# pda6502.net
KiCad netlist of a schematic drawn in EAGLE
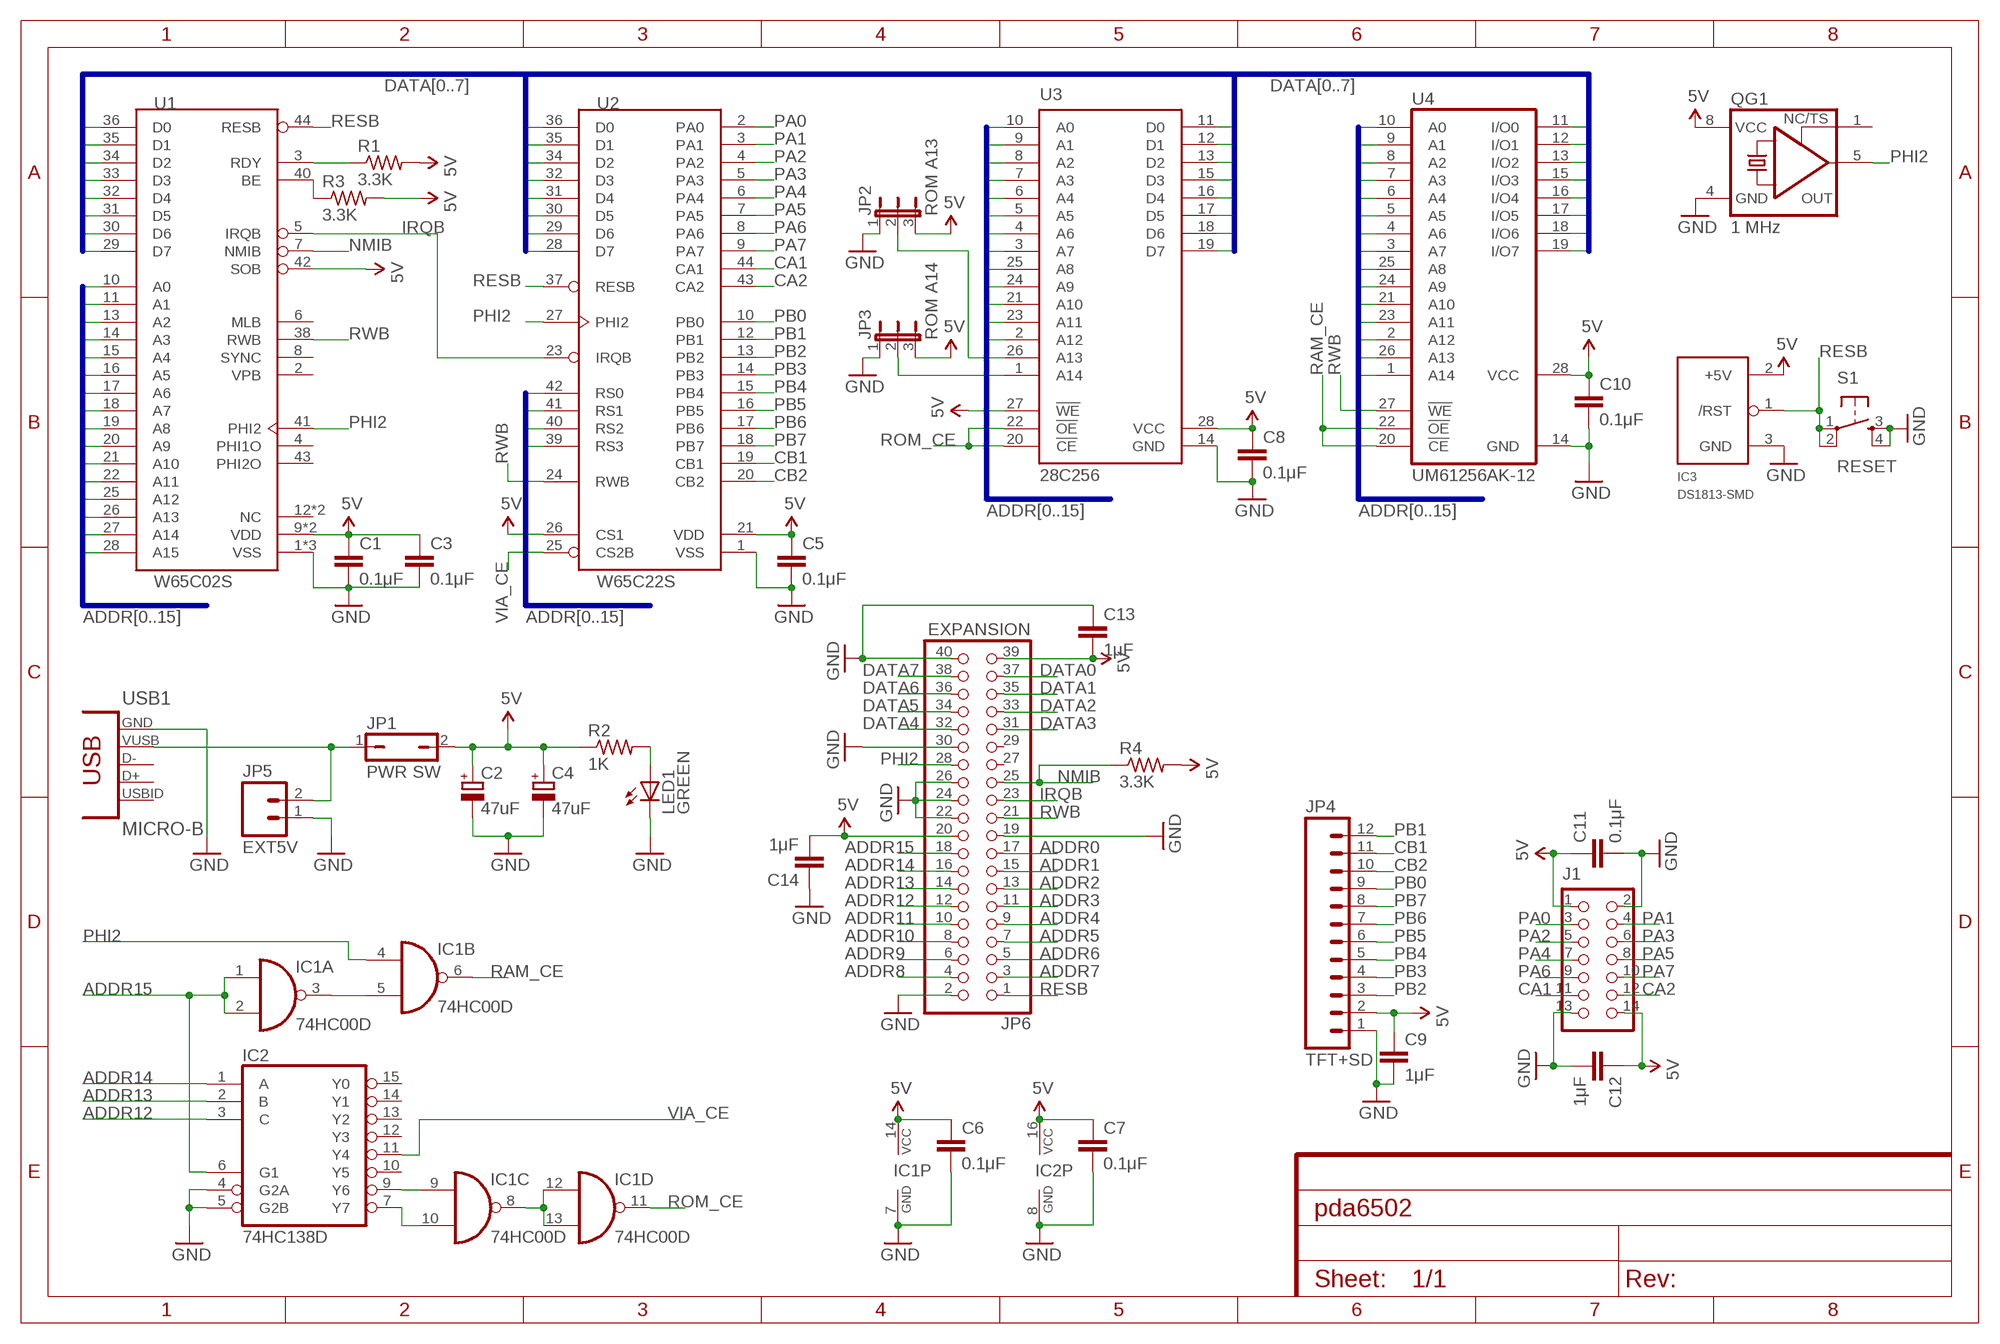
[diagram p0: schematic, sheet 1]

(export (version "E")
  (design (tool "Eeschema 10.0.6"))
  (components
    (comp (ref "C1")
      (value "0.1μF")
      (footprint "eagle-import:C0805")
      (libsource (lib "eagle-import") (part "C-EUC0805"))
    )
    (comp (ref "C2")
      (value "47uF")
      (footprint "eagle-import:CASE_B")
      (libsource (lib "eagle-import") (part "CAPACITOR_POL-CASE_B"))
    )
    (comp (ref "C3")
      (value "0.1μF")
      (footprint "eagle-import:C0805")
      (libsource (lib "eagle-import") (part "C-EUC0805"))
    )
    (comp (ref "C4")
      (value "47uF")
      (footprint "eagle-import:CASE_B")
      (libsource (lib "eagle-import") (part "CAPACITOR_POL-CASE_B"))
    )
    (comp (ref "C5")
      (value "0.1μF")
      (footprint "eagle-import:C0805")
      (libsource (lib "eagle-import") (part "C-EUC0805"))
    )
    (comp (ref "C6")
      (value "0.1μF")
      (footprint "eagle-import:C0805")
      (libsource (lib "eagle-import") (part "C-EUC0805"))
    )
    (comp (ref "C7")
      (value "0.1μF")
      (footprint "eagle-import:C0805")
      (libsource (lib "eagle-import") (part "C-EUC0805"))
    )
    (comp (ref "C8")
      (value "0.1μF")
      (footprint "eagle-import:C0805")
      (libsource (lib "eagle-import") (part "C-EUC0805"))
    )
    (comp (ref "C9")
      (value "1μF")
      (footprint "eagle-import:C0805")
      (libsource (lib "eagle-import") (part "C-EUC0805"))
    )
    (comp (ref "C10")
      (value "0.1μF")
      (footprint "eagle-import:C0805")
      (libsource (lib "eagle-import") (part "C-EUC0805"))
    )
    (comp (ref "C11")
      (value "0.1μF")
      (footprint "eagle-import:C0805")
      (libsource (lib "eagle-import") (part "C-EUC0805"))
    )
    (comp (ref "C12")
      (value "1μF")
      (footprint "eagle-import:C0805")
      (libsource (lib "eagle-import") (part "C-EUC0805"))
    )
    (comp (ref "C13")
      (value "1μF")
      (footprint "eagle-import:C0805")
      (libsource (lib "eagle-import") (part "C-EUC0805"))
    )
    (comp (ref "C14")
      (value "1μF")
      (footprint "eagle-import:C0805")
      (libsource (lib "eagle-import") (part "C-EUC0805"))
    )
    (comp (ref "IC1")
      (value "74HC00D")
      (footprint "eagle-import:SO14")
      (libsource (lib "eagle-import") (part "7400DHC"))
    )
    (comp (ref "IC2")
      (value "74HC138D")
      (footprint "eagle-import:SO16")
      (libsource (lib "eagle-import") (part "74138DHC"))
    )
    (comp (ref "IC3")
      (value "DS1813-SMD")
      (footprint "eagle-import:SOT-23")
      (libsource (lib "eagle-import") (part "DS1813-SMD"))
    )
    (comp (ref "J1")
      (value "CON_HEADER_2X07-PTH")
      (footprint "eagle-import:M2X7")
      (libsource (lib "eagle-import") (part "CON_HEADER_2X07-PTH"))
    )
    (comp (ref "JP1")
      (value "PWR SW")
      (footprint "eagle-import:JMP-1X2")
      (libsource (lib "eagle-import") (part "JMP-1X2TH"))
    )
    (comp (ref "JP2")
      (value "ROM A13")
      (footprint "eagle-import:JP2")
      (libsource (lib "eagle-import") (part "JP2E"))
    )
    (comp (ref "JP3")
      (value "ROM A14")
      (footprint "eagle-import:JP2")
      (libsource (lib "eagle-import") (part "JP2E"))
    )
    (comp (ref "JP4")
      (value "TFT+SD")
      (footprint "eagle-import:1X12_NO_SILK_KIT")
      (libsource (lib "eagle-import") (part "M121X12_NO_SILK_KIT"))
    )
    (comp (ref "JP5")
      (value "EXT5V")
      (footprint "eagle-import:1X02")
      (libsource (lib "eagle-import") (part "M02PTH"))
    )
    (comp (ref "JP6")
      (value "EXPANSION")
      (footprint "eagle-import:2X20")
      (libsource (lib "eagle-import") (part "PINHD-2X20"))
    )
    (comp (ref "LED1")
      (value "GREEN")
      (footprint "eagle-import:LED-805")
      (libsource (lib "eagle-import") (part "LED-0805"))
    )
    (comp (ref "QG1")
      (value "1 MHz")
      (footprint "eagle-import:DIL08S")
      (libsource (lib "eagle-import") (part "XO-8"))
    )
    (comp (ref "R1")
      (value "3.3K")
      (footprint "eagle-import:R0805")
      (libsource (lib "eagle-import") (part "R-US_R0805"))
    )
    (comp (ref "R2")
      (value "1K")
      (footprint "eagle-import:R0805")
      (libsource (lib "eagle-import") (part "R-US_R0805"))
    )
    (comp (ref "R3")
      (value "3.3K")
      (footprint "eagle-import:R0805")
      (libsource (lib "eagle-import") (part "R-US_R0805"))
    )
    (comp (ref "R4")
      (value "3.3K")
      (footprint "eagle-import:R0805")
      (libsource (lib "eagle-import") (part "R-US_R0805"))
    )
    (comp (ref "S1")
      (value "RESET")
      (footprint "eagle-import:TACTILE-SWITCH-SMD")
      (libsource (lib "eagle-import") (part "TAC_SWITCHSMD"))
    )
    (comp (ref "U1")
      (value "W65C02S")
      (footprint "eagle-import:PLCC44-SOCKET")
      (libsource (lib "eagle-import") (part "W65C02PLCC44"))
    )
    (comp (ref "U2")
      (value "W65C22S")
      (footprint "eagle-import:PLCC44-SOCKET")
      (libsource (lib "eagle-import") (part "W65C22PLCC44-SOCKET"))
    )
    (comp (ref "U3")
      (value "28C256")
      (footprint "eagle-import:ZIF28-6-WIDE")
      (libsource (lib "eagle-import") (part "28C256-ZIF"))
    )
    (comp (ref "U4")
      (value "UM61256AK-12")
      (footprint "eagle-import:DIL28-3")
      (libsource (lib "eagle-import") (part "UM61256AK-12"))
    )
    (comp (ref "USB1")
      (value "MICRO-B")
      (footprint "eagle-import:CONN_USB_MICRO-B")
      (libsource (lib "eagle-import") (part "CON-USB-F-MICRO-B"))
    )
  )
  (nets
    (net (code "1") (name "/ADDR0") (class "Default")
      (node (ref "JP6") (pin "17") (pinfunction "17_17") (pintype "passive"))
      (node (ref "U1") (pin "10") (pinfunction "A0_10") (pintype "output"))
      (node (ref "U2") (pin "42") (pinfunction "RS0_42") (pintype "input"))
      (node (ref "U3") (pin "10") (pinfunction "A0_10") (pintype "input"))
      (node (ref "U4") (pin "10") (pinfunction "A0_10") (pintype "input"))
    )
    (net (code "2") (name "/ADDR1") (class "Default")
      (node (ref "JP6") (pin "15") (pinfunction "15_15") (pintype "passive"))
      (node (ref "U1") (pin "11") (pinfunction "A1_11") (pintype "output"))
      (node (ref "U2") (pin "41") (pinfunction "RS1_41") (pintype "input"))
      (node (ref "U3") (pin "9") (pinfunction "A1_9") (pintype "input"))
      (node (ref "U4") (pin "9") (pinfunction "A1_9") (pintype "input"))
    )
    (net (code "3") (name "/ADDR2") (class "Default")
      (node (ref "JP6") (pin "13") (pinfunction "13_13") (pintype "passive"))
      (node (ref "U1") (pin "13") (pinfunction "A2_13") (pintype "output"))
      (node (ref "U2") (pin "40") (pinfunction "RS2_40") (pintype "input"))
      (node (ref "U3") (pin "8") (pinfunction "A2_8") (pintype "input"))
      (node (ref "U4") (pin "8") (pinfunction "A2_8") (pintype "input"))
    )
    (net (code "4") (name "/ADDR3") (class "Default")
      (node (ref "JP6") (pin "11") (pinfunction "11_11") (pintype "passive"))
      (node (ref "U1") (pin "14") (pinfunction "A3_14") (pintype "output"))
      (node (ref "U2") (pin "39") (pinfunction "RS3_39") (pintype "input"))
      (node (ref "U3") (pin "7") (pinfunction "A3_7") (pintype "input"))
      (node (ref "U4") (pin "7") (pinfunction "A3_7") (pintype "input"))
    )
    (net (code "5") (name "/ADDR4") (class "Default")
      (node (ref "JP6") (pin "9") (pinfunction "9_9") (pintype "passive"))
      (node (ref "U1") (pin "15") (pinfunction "A4_15") (pintype "output"))
      (node (ref "U3") (pin "6") (pinfunction "A4_6") (pintype "input"))
      (node (ref "U4") (pin "6") (pinfunction "A4_6") (pintype "input"))
    )
    (net (code "6") (name "/ADDR5") (class "Default")
      (node (ref "JP6") (pin "7") (pinfunction "7_7") (pintype "passive"))
      (node (ref "U1") (pin "16") (pinfunction "A5_16") (pintype "output"))
      (node (ref "U3") (pin "5") (pinfunction "A5_5") (pintype "input"))
      (node (ref "U4") (pin "5") (pinfunction "A5_5") (pintype "input"))
    )
    (net (code "7") (name "/ADDR6") (class "Default")
      (node (ref "JP6") (pin "5") (pinfunction "5_5") (pintype "passive"))
      (node (ref "U1") (pin "17") (pinfunction "A6_17") (pintype "output"))
      (node (ref "U3") (pin "4") (pinfunction "A6_4") (pintype "input"))
      (node (ref "U4") (pin "4") (pinfunction "A6_4") (pintype "input"))
    )
    (net (code "8") (name "/ADDR7") (class "Default")
      (node (ref "JP6") (pin "3") (pinfunction "3_3") (pintype "passive"))
      (node (ref "U1") (pin "18") (pinfunction "A7_18") (pintype "output"))
      (node (ref "U3") (pin "3") (pinfunction "A7_3") (pintype "input"))
      (node (ref "U4") (pin "3") (pinfunction "A7_3") (pintype "input"))
    )
    (net (code "9") (name "/ADDR8") (class "Default")
      (node (ref "JP6") (pin "4") (pinfunction "4_4") (pintype "passive"))
      (node (ref "U1") (pin "19") (pinfunction "A8_19") (pintype "output"))
      (node (ref "U3") (pin "25") (pinfunction "A8_25") (pintype "input"))
      (node (ref "U4") (pin "25") (pinfunction "A8_25") (pintype "input"))
    )
    (net (code "10") (name "/ADDR9") (class "Default")
      (node (ref "JP6") (pin "6") (pinfunction "6_6") (pintype "passive"))
      (node (ref "U1") (pin "20") (pinfunction "A9_20") (pintype "output"))
      (node (ref "U3") (pin "24") (pinfunction "A9_24") (pintype "input"))
      (node (ref "U4") (pin "24") (pinfunction "A9_24") (pintype "input"))
    )
    (net (code "11") (name "/ADDR10") (class "Default")
      (node (ref "JP6") (pin "8") (pinfunction "8_8") (pintype "passive"))
      (node (ref "U1") (pin "21") (pinfunction "A10_21") (pintype "output"))
      (node (ref "U3") (pin "21") (pinfunction "A10_21") (pintype "input"))
      (node (ref "U4") (pin "21") (pinfunction "A10_21") (pintype "input"))
    )
    (net (code "12") (name "/ADDR11") (class "Default")
      (node (ref "JP6") (pin "10") (pinfunction "10_10") (pintype "passive"))
      (node (ref "U1") (pin "22") (pinfunction "A11_22") (pintype "output"))
      (node (ref "U3") (pin "23") (pinfunction "A11_23") (pintype "input"))
      (node (ref "U4") (pin "23") (pinfunction "A11_23") (pintype "input"))
    )
    (net (code "13") (name "/ADDR12") (class "Default")
      (node (ref "IC2") (pin "3") (pinfunction "C_3") (pintype "input"))
      (node (ref "JP6") (pin "12") (pinfunction "12_12") (pintype "passive"))
      (node (ref "U1") (pin "25") (pinfunction "A12_25") (pintype "output"))
      (node (ref "U3") (pin "2") (pinfunction "A12_2") (pintype "input"))
      (node (ref "U4") (pin "2") (pinfunction "A12_2") (pintype "input"))
    )
    (net (code "14") (name "/ADDR13") (class "Default")
      (node (ref "IC2") (pin "2") (pinfunction "B_2") (pintype "input"))
      (node (ref "JP6") (pin "14") (pinfunction "14_14") (pintype "passive"))
      (node (ref "U1") (pin "26") (pinfunction "A13_26") (pintype "output"))
      (node (ref "U4") (pin "26") (pinfunction "A13_26") (pintype "input"))
    )
    (net (code "15") (name "/ADDR14") (class "Default")
      (node (ref "IC2") (pin "1") (pinfunction "A_1") (pintype "input"))
      (node (ref "JP6") (pin "16") (pinfunction "16_16") (pintype "passive"))
      (node (ref "U1") (pin "27") (pinfunction "A14_27") (pintype "output"))
      (node (ref "U4") (pin "1") (pinfunction "A14_1") (pintype "input"))
    )
    (net (code "16") (name "/ADDR15") (class "Default")
      (node (ref "IC1") (pin "1") (pinfunction "I0_1") (pintype "input"))
      (node (ref "IC1") (pin "2") (pinfunction "I1_2") (pintype "input"))
      (node (ref "IC2") (pin "6") (pinfunction "G1_6") (pintype "input"))
      (node (ref "JP6") (pin "18") (pinfunction "18_18") (pintype "passive"))
      (node (ref "U1") (pin "28") (pinfunction "A15_28") (pintype "output"))
    )
    (net (code "18") (name "/CA1") (class "Default")
      (node (ref "J1") (pin "11") (pinfunction "11_11") (pintype "passive"))
      (node (ref "U2") (pin "44") (pinfunction "CA1_44") (pintype "input"))
    )
    (net (code "19") (name "/CA2") (class "Default")
      (node (ref "J1") (pin "12") (pinfunction "12_12") (pintype "passive"))
      (node (ref "U2") (pin "43") (pinfunction "CA2_43") (pintype "bidirectional"))
    )
    (net (code "20") (name "/CB1") (class "Default")
      (node (ref "JP4") (pin "11") (pinfunction "11_11") (pintype "passive"))
      (node (ref "U2") (pin "19") (pinfunction "CB1_19") (pintype "input"))
    )
    (net (code "21") (name "/CB2") (class "Default")
      (node (ref "JP4") (pin "10") (pinfunction "10_10") (pintype "passive"))
      (node (ref "U2") (pin "20") (pinfunction "CB2_20") (pintype "bidirectional"))
    )
    (net (code "22") (name "/DATA0") (class "Default")
      (node (ref "JP6") (pin "37") (pinfunction "37_37") (pintype "passive"))
      (node (ref "U1") (pin "36") (pinfunction "D0_36") (pintype "bidirectional"))
      (node (ref "U2") (pin "36") (pinfunction "D0_36") (pintype "bidirectional"))
      (node (ref "U3") (pin "11") (pinfunction "D0_11") (pintype "tri_state"))
      (node (ref "U4") (pin "11") (pinfunction "I/O0_11") (pintype "bidirectional"))
    )
    (net (code "23") (name "/DATA1") (class "Default")
      (node (ref "JP6") (pin "35") (pinfunction "35_35") (pintype "passive"))
      (node (ref "U1") (pin "35") (pinfunction "D1_35") (pintype "bidirectional"))
      (node (ref "U2") (pin "35") (pinfunction "D1_35") (pintype "bidirectional"))
      (node (ref "U3") (pin "12") (pinfunction "D1_12") (pintype "tri_state"))
      (node (ref "U4") (pin "12") (pinfunction "I/O1_12") (pintype "bidirectional"))
    )
    (net (code "24") (name "/DATA2") (class "Default")
      (node (ref "JP6") (pin "33") (pinfunction "33_33") (pintype "passive"))
      (node (ref "U1") (pin "34") (pinfunction "D2_34") (pintype "bidirectional"))
      (node (ref "U2") (pin "34") (pinfunction "D2_34") (pintype "bidirectional"))
      (node (ref "U3") (pin "13") (pinfunction "D2_13") (pintype "tri_state"))
      (node (ref "U4") (pin "13") (pinfunction "I/O2_13") (pintype "bidirectional"))
    )
    (net (code "25") (name "/DATA3") (class "Default")
      (node (ref "JP6") (pin "31") (pinfunction "31_31") (pintype "passive"))
      (node (ref "U1") (pin "33") (pinfunction "D3_33") (pintype "bidirectional"))
      (node (ref "U2") (pin "32") (pinfunction "D3_32") (pintype "bidirectional"))
      (node (ref "U3") (pin "15") (pinfunction "D3_15") (pintype "tri_state"))
      (node (ref "U4") (pin "15") (pinfunction "I/O3_15") (pintype "bidirectional"))
    )
    (net (code "26") (name "/DATA4") (class "Default")
      (node (ref "JP6") (pin "32") (pinfunction "32_32") (pintype "passive"))
      (node (ref "U1") (pin "32") (pinfunction "D4_32") (pintype "bidirectional"))
      (node (ref "U2") (pin "31") (pinfunction "D4_31") (pintype "bidirectional"))
      (node (ref "U3") (pin "16") (pinfunction "D4_16") (pintype "tri_state"))
      (node (ref "U4") (pin "16") (pinfunction "I/O4_16") (pintype "bidirectional"))
    )
    (net (code "27") (name "/DATA5") (class "Default")
      (node (ref "JP6") (pin "34") (pinfunction "34_34") (pintype "passive"))
      (node (ref "U1") (pin "31") (pinfunction "D5_31") (pintype "bidirectional"))
      (node (ref "U2") (pin "30") (pinfunction "D5_30") (pintype "bidirectional"))
      (node (ref "U3") (pin "17") (pinfunction "D5_17") (pintype "tri_state"))
      (node (ref "U4") (pin "17") (pinfunction "I/O5_17") (pintype "bidirectional"))
    )
    (net (code "28") (name "/DATA6") (class "Default")
      (node (ref "JP6") (pin "36") (pinfunction "36_36") (pintype "passive"))
      (node (ref "U1") (pin "30") (pinfunction "D6_30") (pintype "bidirectional"))
      (node (ref "U2") (pin "29") (pinfunction "D6_29") (pintype "bidirectional"))
      (node (ref "U3") (pin "18") (pinfunction "D6_18") (pintype "tri_state"))
      (node (ref "U4") (pin "18") (pinfunction "I/O6_18") (pintype "bidirectional"))
    )
    (net (code "29") (name "/DATA7") (class "Default")
      (node (ref "JP6") (pin "38") (pinfunction "38_38") (pintype "passive"))
      (node (ref "U1") (pin "29") (pinfunction "D7_29") (pintype "bidirectional"))
      (node (ref "U2") (pin "28") (pinfunction "D7_28") (pintype "bidirectional"))
      (node (ref "U3") (pin "19") (pinfunction "D7_19") (pintype "tri_state"))
      (node (ref "U4") (pin "19") (pinfunction "I/O7_19") (pintype "bidirectional"))
    )
    (net (code "31") (name "/IRQB") (class "Default")
      (node (ref "JP6") (pin "23") (pinfunction "23_23") (pintype "passive"))
      (node (ref "U1") (pin "5") (pinfunction "IRQB_5") (pintype "input"))
      (node (ref "U2") (pin "23") (pinfunction "IRQB_23") (pintype "open_collector"))
    )
    (net (code "32") (name "/NMIB") (class "Default")
      (node (ref "JP6") (pin "25") (pinfunction "25_25") (pintype "passive"))
      (node (ref "R4") (pin "1") (pinfunction "1_1") (pintype "passive"))
      (node (ref "U1") (pin "7") (pinfunction "NMIB_7") (pintype "input"))
    )
    (net (code "33") (name "/PA0") (class "Default")
      (node (ref "J1") (pin "3") (pinfunction "3_3") (pintype "passive"))
      (node (ref "U2") (pin "2") (pinfunction "PA0_2") (pintype "bidirectional"))
    )
    (net (code "34") (name "/PA1") (class "Default")
      (node (ref "J1") (pin "4") (pinfunction "4_4") (pintype "passive"))
      (node (ref "U2") (pin "3") (pinfunction "PA1_3") (pintype "bidirectional"))
    )
    (net (code "35") (name "/PA2") (class "Default")
      (node (ref "J1") (pin "5") (pinfunction "5_5") (pintype "passive"))
      (node (ref "U2") (pin "4") (pinfunction "PA2_4") (pintype "bidirectional"))
    )
    (net (code "36") (name "/PA3") (class "Default")
      (node (ref "J1") (pin "6") (pinfunction "6_6") (pintype "passive"))
      (node (ref "U2") (pin "5") (pinfunction "PA3_5") (pintype "bidirectional"))
    )
    (net (code "37") (name "/PA4") (class "Default")
      (node (ref "J1") (pin "7") (pinfunction "7_7") (pintype "passive"))
      (node (ref "U2") (pin "6") (pinfunction "PA4_6") (pintype "bidirectional"))
    )
    (net (code "38") (name "/PA5") (class "Default")
      (node (ref "J1") (pin "8") (pinfunction "8_8") (pintype "passive"))
      (node (ref "U2") (pin "7") (pinfunction "PA5_7") (pintype "bidirectional"))
    )
    (net (code "39") (name "/PA6") (class "Default")
      (node (ref "J1") (pin "9") (pinfunction "9_9") (pintype "passive"))
      (node (ref "U2") (pin "8") (pinfunction "PA6_8") (pintype "bidirectional"))
    )
    (net (code "40") (name "/PA7") (class "Default")
      (node (ref "J1") (pin "10") (pinfunction "10_10") (pintype "passive"))
      (node (ref "U2") (pin "9") (pinfunction "PA7_9") (pintype "bidirectional"))
    )
    (net (code "41") (name "/PB0") (class "Default")
      (node (ref "JP4") (pin "9") (pinfunction "9_9") (pintype "passive"))
      (node (ref "U2") (pin "10") (pinfunction "PB0_10") (pintype "bidirectional"))
    )
    (net (code "42") (name "/PB1") (class "Default")
      (node (ref "JP4") (pin "12") (pinfunction "12_12") (pintype "passive"))
      (node (ref "U2") (pin "12") (pinfunction "PB1_12") (pintype "bidirectional"))
    )
    (net (code "43") (name "/PB2") (class "Default")
      (node (ref "JP4") (pin "3") (pinfunction "3_3") (pintype "passive"))
      (node (ref "U2") (pin "13") (pinfunction "PB2_13") (pintype "bidirectional"))
    )
    (net (code "44") (name "/PB3") (class "Default")
      (node (ref "JP4") (pin "4") (pinfunction "4_4") (pintype "passive"))
      (node (ref "U2") (pin "14") (pinfunction "PB3_14") (pintype "bidirectional"))
    )
    (net (code "45") (name "/PB4") (class "Default")
      (node (ref "JP4") (pin "5") (pinfunction "5_5") (pintype "passive"))
      (node (ref "U2") (pin "15") (pinfunction "PB4_15") (pintype "bidirectional"))
    )
    (net (code "46") (name "/PB5") (class "Default")
      (node (ref "JP4") (pin "6") (pinfunction "6_6") (pintype "passive"))
      (node (ref "U2") (pin "16") (pinfunction "PB5_16") (pintype "bidirectional"))
    )
    (net (code "47") (name "/PB6") (class "Default")
      (node (ref "JP4") (pin "7") (pinfunction "7_7") (pintype "passive"))
      (node (ref "U2") (pin "17") (pinfunction "PB6_17") (pintype "bidirectional"))
    )
    (net (code "48") (name "/PB7") (class "Default")
      (node (ref "JP4") (pin "8") (pinfunction "8_8") (pintype "passive"))
      (node (ref "U2") (pin "18") (pinfunction "PB7_18") (pintype "bidirectional"))
    )
    (net (code "49") (name "/PHI2") (class "Default")
      (node (ref "IC1") (pin "4") (pinfunction "I0_4") (pintype "input"))
      (node (ref "JP6") (pin "28") (pinfunction "28_28") (pintype "passive"))
      (node (ref "QG1") (pin "5") (pinfunction "OUT_5") (pintype "output"))
      (node (ref "U1") (pin "41") (pinfunction "PHI2_41") (pintype "input"))
      (node (ref "U2") (pin "27") (pinfunction "PHI2_27") (pintype "input"))
    )
    (net (code "50") (name "/RAM_CE") (class "Default")
      (node (ref "IC1") (pin "6") (pinfunction "O_6") (pintype "output"))
      (node (ref "U4") (pin "20") (pinfunction "~{CE}_20") (pintype "input"))
      (node (ref "U4") (pin "22") (pinfunction "~{OE}_22") (pintype "input"))
    )
    (net (code "51") (name "/RESB") (class "Default")
      (node (ref "IC3") (pin "1") (pinfunction "/RST_1") (pintype "passive"))
      (node (ref "JP6") (pin "1") (pinfunction "1_1") (pintype "passive"))
      (node (ref "S1") (pin "1") (pinfunction "1_1") (pintype "passive"))
      (node (ref "S1") (pin "2") (pinfunction "2_2") (pintype "passive"))
      (node (ref "U1") (pin "44") (pinfunction "RESB_44") (pintype "input"))
      (node (ref "U2") (pin "37") (pinfunction "RESB_37") (pintype "input"))
    )
    (net (code "52") (name "/ROM_CE") (class "Default")
      (node (ref "IC1") (pin "11") (pinfunction "O_11") (pintype "output"))
      (node (ref "U3") (pin "20") (pinfunction "~{CE}_20") (pintype "input"))
      (node (ref "U3") (pin "22") (pinfunction "~{OE}_22") (pintype "input"))
    )
    (net (code "53") (name "/RWB") (class "Default")
      (node (ref "JP6") (pin "21") (pinfunction "21_21") (pintype "passive"))
      (node (ref "U1") (pin "38") (pinfunction "RWB_38") (pintype "output"))
      (node (ref "U2") (pin "24") (pinfunction "RWB_24") (pintype "input"))
      (node (ref "U4") (pin "27") (pinfunction "~{WE}_27") (pintype "input"))
    )
    (net (code "54") (name "/VIA_CE") (class "Default")
      (node (ref "IC2") (pin "11") (pinfunction "Y4_11") (pintype "output"))
      (node (ref "U2") (pin "25") (pinfunction "CS2B_25") (pintype "input"))
    )
    (net (code "55") (name "5V") (class "Default")
      (node (ref "C1") (pin "1") (pinfunction "1_1") (pintype "passive"))
      (node (ref "C10") (pin "1") (pinfunction "1_1") (pintype "passive"))
      (node (ref "C11") (pin "1") (pinfunction "1_1") (pintype "passive"))
      (node (ref "C12") (pin "1") (pinfunction "1_1") (pintype "passive"))
      (node (ref "C13") (pin "2") (pinfunction "2_2") (pintype "passive"))
      (node (ref "C14") (pin "2") (pinfunction "2_2") (pintype "passive"))
      (node (ref "C2") (pin "+") (pinfunction "+_+") (pintype "passive"))
      (node (ref "C3") (pin "1") (pinfunction "1_1") (pintype "passive"))
      (node (ref "C4") (pin "+") (pinfunction "+_+") (pintype "passive"))
      (node (ref "C5") (pin "1") (pinfunction "1_1") (pintype "passive"))
      (node (ref "C6") (pin "1") (pinfunction "1_1") (pintype "passive"))
      (node (ref "C7") (pin "1") (pinfunction "1_1") (pintype "passive"))
      (node (ref "C8") (pin "1") (pinfunction "1_1") (pintype "passive"))
      (node (ref "C9") (pin "1") (pinfunction "1_1") (pintype "passive"))
      (node (ref "IC1") (pin "14") (pinfunction "VCC_14") (pintype "power_in"))
      (node (ref "IC2") (pin "16") (pinfunction "VCC_16") (pintype "power_in"))
      (node (ref "IC3") (pin "2") (pinfunction "+5V_2") (pintype "power_in"))
      (node (ref "J1") (pin "1") (pinfunction "1_1") (pintype "passive"))
      (node (ref "J1") (pin "14") (pinfunction "14_14") (pintype "passive"))
      (node (ref "JP1") (pin "2") (pinfunction "2_2") (pintype "passive"))
      (node (ref "JP2") (pin "3") (pinfunction "3_3") (pintype "passive"))
      (node (ref "JP3") (pin "3") (pinfunction "3_3") (pintype "passive"))
      (node (ref "JP4") (pin "2") (pinfunction "2_2") (pintype "passive"))
      (node (ref "JP6") (pin "20") (pinfunction "20_20") (pintype "passive"))
      (node (ref "JP6") (pin "39") (pinfunction "39_39") (pintype "passive"))
      (node (ref "QG1") (pin "8") (pinfunction "VCC_8") (pintype "power_in"))
      (node (ref "R1") (pin "2") (pinfunction "2_2") (pintype "passive"))
      (node (ref "R2") (pin "1") (pinfunction "1_1") (pintype "passive"))
      (node (ref "R3") (pin "2") (pinfunction "2_2") (pintype "passive"))
      (node (ref "R4") (pin "2") (pinfunction "2_2") (pintype "passive"))
      (node (ref "U1") (pin "37") (pinfunction "VDD_37") (pintype "power_in"))
      (node (ref "U1") (pin "42") (pinfunction "SOB_42") (pintype "input"))
      (node (ref "U1") (pin "9") (pinfunction "VDD_9") (pintype "power_in"))
      (node (ref "U2") (pin "21") (pinfunction "VDD_21") (pintype "power_in"))
      (node (ref "U2") (pin "26") (pinfunction "CS1_26") (pintype "input"))
      (node (ref "U3") (pin "27") (pinfunction "~{WE}_27") (pintype "input"))
      (node (ref "U3") (pin "28") (pinfunction "VCC_28") (pintype "power_in"))
      (node (ref "U4") (pin "28") (pinfunction "VCC_28") (pintype "power_in"))
    )
    (net (code "56") (name "GND") (class "Default")
      (node (ref "C1") (pin "2") (pinfunction "2_2") (pintype "passive"))
      (node (ref "C10") (pin "2") (pinfunction "2_2") (pintype "passive"))
      (node (ref "C11") (pin "2") (pinfunction "2_2") (pintype "passive"))
      (node (ref "C12") (pin "2") (pinfunction "2_2") (pintype "passive"))
      (node (ref "C13") (pin "1") (pinfunction "1_1") (pintype "passive"))
      (node (ref "C14") (pin "1") (pinfunction "1_1") (pintype "passive"))
      (node (ref "C2") (pin "-") (pinfunction "-_-") (pintype "passive"))
      (node (ref "C3") (pin "2") (pinfunction "2_2") (pintype "passive"))
      (node (ref "C4") (pin "-") (pinfunction "-_-") (pintype "passive"))
      (node (ref "C5") (pin "2") (pinfunction "2_2") (pintype "passive"))
      (node (ref "C6") (pin "2") (pinfunction "2_2") (pintype "passive"))
      (node (ref "C7") (pin "2") (pinfunction "2_2") (pintype "passive"))
      (node (ref "C8") (pin "2") (pinfunction "2_2") (pintype "passive"))
      (node (ref "C9") (pin "2") (pinfunction "2_2") (pintype "passive"))
      (node (ref "IC1") (pin "7") (pinfunction "GND_7") (pintype "power_in"))
      (node (ref "IC2") (pin "4") (pinfunction "G2A_4") (pintype "input"))
      (node (ref "IC2") (pin "5") (pinfunction "G2B_5") (pintype "input"))
      (node (ref "IC2") (pin "8") (pinfunction "GND_8") (pintype "power_in"))
      (node (ref "IC3") (pin "3") (pinfunction "GND_3") (pintype "power_in"))
      (node (ref "J1") (pin "13") (pinfunction "13_13") (pintype "passive"))
      (node (ref "J1") (pin "2") (pinfunction "2_2") (pintype "passive"))
      (node (ref "JP2") (pin "1") (pinfunction "1_1") (pintype "passive"))
      (node (ref "JP3") (pin "1") (pinfunction "1_1") (pintype "passive"))
      (node (ref "JP4") (pin "1") (pinfunction "1_1") (pintype "passive"))
      (node (ref "JP5") (pin "1") (pinfunction "1_1") (pintype "passive"))
      (node (ref "JP6") (pin "19") (pinfunction "19_19") (pintype "passive"))
      (node (ref "JP6") (pin "2") (pinfunction "2_2") (pintype "passive"))
      (node (ref "JP6") (pin "22") (pinfunction "22_22") (pintype "passive"))
      (node (ref "JP6") (pin "24") (pinfunction "24_24") (pintype "passive"))
      (node (ref "JP6") (pin "26") (pinfunction "26_26") (pintype "passive"))
      (node (ref "JP6") (pin "30") (pinfunction "30_30") (pintype "passive"))
      (node (ref "JP6") (pin "40") (pinfunction "40_40") (pintype "passive"))
      (node (ref "LED1") (pin "C") (pinfunction "C_C") (pintype "passive"))
      (node (ref "QG1") (pin "4") (pinfunction "GND_4") (pintype "power_in"))
      (node (ref "S1") (pin "3") (pinfunction "3_3") (pintype "passive"))
      (node (ref "S1") (pin "4") (pinfunction "4_4") (pintype "passive"))
      (node (ref "U1") (pin "1") (pinfunction "VSS_1") (pintype "power_in"))
      (node (ref "U1") (pin "23") (pinfunction "VSS_23") (pintype "power_in"))
      (node (ref "U1") (pin "24") (pinfunction "VSS_24") (pintype "power_in"))
      (node (ref "U2") (pin "1") (pinfunction "VSS_1") (pintype "power_in"))
      (node (ref "U3") (pin "14") (pinfunction "GND_14") (pintype "power_in"))
      (node (ref "U4") (pin "14") (pinfunction "GND_14") (pintype "power_in"))
      (node (ref "USB1") (pin "P5") (pinfunction "GND_P5") (pintype "bidirectional"))
    )
    (net (code "57") (name "Net-(IC1A-O)") (class "Default")
      (node (ref "IC1") (pin "3") (pinfunction "O_3") (pintype "output"))
      (node (ref "IC1") (pin "5") (pinfunction "I1_5") (pintype "input"))
    )
    (net (code "58") (name "Net-(IC1C-I0)") (class "Default")
      (node (ref "IC1") (pin "9") (pinfunction "I0_9") (pintype "input"))
      (node (ref "IC2") (pin "9") (pinfunction "Y6_9") (pintype "output"))
    )
    (net (code "59") (name "Net-(IC1C-I1)") (class "Default")
      (node (ref "IC1") (pin "10") (pinfunction "I1_10") (pintype "input"))
      (node (ref "IC2") (pin "7") (pinfunction "Y7_7") (pintype "output"))
    )
    (net (code "60") (name "Net-(IC1C-O)") (class "Default")
      (node (ref "IC1") (pin "12") (pinfunction "I0_12") (pintype "input"))
      (node (ref "IC1") (pin "13") (pinfunction "I1_13") (pintype "input"))
      (node (ref "IC1") (pin "8") (pinfunction "O_8") (pintype "output"))
    )
    (net (code "61") (name "Net-(LED1-PadA)") (class "Default")
      (node (ref "LED1") (pin "A") (pinfunction "A_A") (pintype "passive"))
      (node (ref "R2") (pin "2") (pinfunction "2_2") (pintype "passive"))
    )
    (net (code "62") (name "Net-(U1-BE)") (class "Default")
      (node (ref "R3") (pin "1") (pinfunction "1_1") (pintype "passive"))
      (node (ref "U1") (pin "40") (pinfunction "BE_40") (pintype "input"))
    )
    (net (code "63") (name "Net-(U1-RDY)") (class "Default")
      (node (ref "R1") (pin "1") (pinfunction "1_1") (pintype "passive"))
      (node (ref "U1") (pin "3") (pinfunction "RDY_3") (pintype "input"))
    )
    (net (code "64") (name "Net-(U3-A13)") (class "Default")
      (node (ref "JP2") (pin "2") (pinfunction "2_2") (pintype "passive"))
      (node (ref "U3") (pin "26") (pinfunction "A13_26") (pintype "input"))
    )
    (net (code "65") (name "Net-(U3-A14)") (class "Default")
      (node (ref "JP3") (pin "2") (pinfunction "2_2") (pintype "passive"))
      (node (ref "U3") (pin "1") (pinfunction "A14_1") (pintype "input"))
    )
    (net (code "66") (name "Net-(USB1B-VUSB)") (class "Default")
      (node (ref "JP1") (pin "1") (pinfunction "1_1") (pintype "passive"))
      (node (ref "JP5") (pin "2") (pinfunction "2_2") (pintype "passive"))
      (node (ref "USB1") (pin "P1") (pinfunction "VUSB_P1") (pintype "bidirectional"))
    )
    (net (code "67") (name "unconnected-(IC2A-Y0-Pad15)") (class "Default")
      (node (ref "IC2") (pin "15") (pinfunction "Y0_15") (pintype "output"))
    )
    (net (code "68") (name "unconnected-(IC2A-Y1-Pad14)") (class "Default")
      (node (ref "IC2") (pin "14") (pinfunction "Y1_14") (pintype "output"))
    )
    (net (code "69") (name "unconnected-(IC2A-Y2-Pad13)") (class "Default")
      (node (ref "IC2") (pin "13") (pinfunction "Y2_13") (pintype "output"))
    )
    (net (code "70") (name "unconnected-(IC2A-Y3-Pad12)") (class "Default")
      (node (ref "IC2") (pin "12") (pinfunction "Y3_12") (pintype "output"))
    )
    (net (code "71") (name "unconnected-(IC2A-Y5-Pad10)") (class "Default")
      (node (ref "IC2") (pin "10") (pinfunction "Y5_10") (pintype "output"))
    )
    (net (code "72") (name "unconnected-(JP6-Pad27)") (class "Default")
      (node (ref "JP6") (pin "27") (pinfunction "27_27") (pintype "passive"))
    )
    (net (code "73") (name "unconnected-(JP6-Pad29)") (class "Default")
      (node (ref "JP6") (pin "29") (pinfunction "29_29") (pintype "passive"))
    )
    (net (code "74") (name "unconnected-(QG1-TS-Pad1)") (class "Default")
      (node (ref "QG1") (pin "1") (pinfunction "TS_1") (pintype "passive"))
    )
    (net (code "75") (name "unconnected-(U1-MLB-Pad6)") (class "Default")
      (node (ref "U1") (pin "6") (pinfunction "MLB_6") (pintype "output"))
    )
    (net (code "76") (name "unconnected-(U1-NC-Pad12)") (class "Default")
      (node (ref "U1") (pin "12") (pinfunction "NC_12") (pintype "no_connect"))
    )
    (net (code "77") (name "unconnected-(U1-NC-Pad39)") (class "Default")
      (node (ref "U1") (pin "39") (pinfunction "NC_39") (pintype "no_connect"))
    )
    (net (code "78") (name "unconnected-(U1-PHI1O-Pad4)") (class "Default")
      (node (ref "U1") (pin "4") (pinfunction "PHI1O_4") (pintype "output"))
    )
    (net (code "79") (name "unconnected-(U1-PHI2O-Pad43)") (class "Default")
      (node (ref "U1") (pin "43") (pinfunction "PHI2O_43") (pintype "output"))
    )
    (net (code "80") (name "unconnected-(U1-SYNC-Pad8)") (class "Default")
      (node (ref "U1") (pin "8") (pinfunction "SYNC_8") (pintype "output"))
    )
    (net (code "81") (name "unconnected-(U1-VPB-Pad2)") (class "Default")
      (node (ref "U1") (pin "2") (pinfunction "VPB_2") (pintype "output"))
    )
    (net (code "82") (name "unconnected-(USB1B-D+-PadP3)") (class "Default")
      (node (ref "USB1") (pin "P3") (pinfunction "D+_P3") (pintype "bidirectional"))
    )
    (net (code "83") (name "unconnected-(USB1B-D--PadP2)") (class "Default")
      (node (ref "USB1") (pin "P2") (pinfunction "D-_P2") (pintype "bidirectional"))
    )
    (net (code "84") (name "unconnected-(USB1B-USBID-PadP4)") (class "Default")
      (node (ref "USB1") (pin "P4") (pinfunction "USBID_P4") (pintype "bidirectional"))
    )
  )
)
